# LED_card.net
KiCad netlist of a schematic drawn in EAGLE
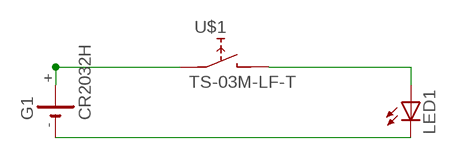
[diagram p0: schematic, sheet 1]

(export (version "E")
  (design (tool "Eeschema 10.0.6"))
  (components
    (comp (ref "G1")
      (value "CR2032H")
      (footprint "eagle-import:CR2032H")
      (libsource (lib "eagle-import") (part "CR2032H"))
    )
    (comp (ref "LED1")
      (value "LED5MM")
      (footprint "eagle-import:LED5MM")
      (libsource (lib "eagle-import") (part "LED5MM"))
    )
    (comp (ref "U$1")
      (value "TS-03M-LF-T")
      (footprint "eagle-import:TS-03M-LF-T")
      (libsource (lib "eagle-import") (part "TS-03M-LF-T"))
    )
  )
  (nets
    (net (code "1") (name "Net-(LED1-C)") (class "Default")
      (node (ref "G1") (pin "-") (pinfunction "-_-") (pintype "passive"))
      (node (ref "LED1") (pin "K") (pinfunction "C_K") (pintype "passive"))
    )
    (net (code "2") (name "Net-(U$1-A1)") (class "Default")
      (node (ref "G1") (pin "+") (pinfunction "+_+") (pintype "passive"))
      (node (ref "G1") (pin "+@1") (pinfunction "+_+@1") (pintype "passive"))
      (node (ref "U$1") (pin "P$1") (pinfunction "A1_P$1") (pintype "passive"))
    )
    (net (code "3") (name "Net-(U$1-B)") (class "Default")
      (node (ref "LED1") (pin "A") (pinfunction "A_A") (pintype "passive"))
      (node (ref "U$1") (pin "P$2") (pinfunction "B_P$2") (pintype "passive"))
    )
  )
)
